# USB_To_UART.net
KiCad netlist of a schematic drawn in Altium Designer
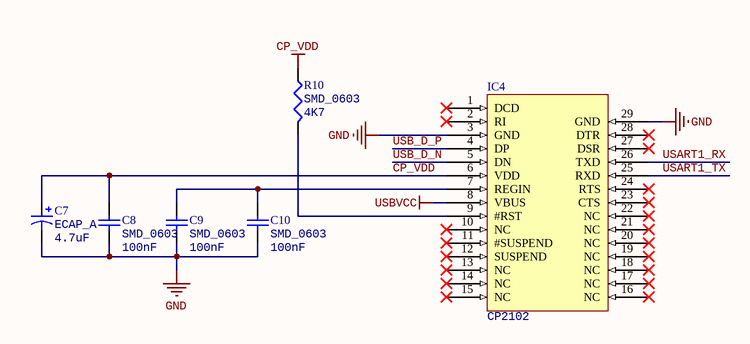
[diagram p0: USB_To_UART.SchDoc]

(export (version "E")
  (design (tool "Eeschema 10.0.6"))
  (components
    (comp (ref "C7")
      (value "ECAP_A")
      (footprint "CAPAE4645X63M")
      (description "Polarized Capacitor (Radial)")
      (fields (field (name "ALTIUM_VALUE") "4.7uF") (field (name "PUBLISHER") "Altium Limited"))
      (libsource (lib "Miscellaneous Devices") (part "Cap Pol1"))
    )
    (comp (ref "C8")
      (value "SMD_0603")
      (footprint "1608[0603]")
      (description "Capacitor (Semiconductor SIM Model)")
      (fields (field (name "ALTIUM_VALUE") "100nF") (field (name "PUBLISHER") "Altium Limited"))
      (libsource (lib "Miscellaneous Devices") (part "Cap Semi"))
    )
    (comp (ref "C9")
      (value "SMD_0603")
      (footprint "1608[0603]")
      (description "Capacitor (Semiconductor SIM Model)")
      (fields (field (name "ALTIUM_VALUE") "100nF") (field (name "PUBLISHER") "Altium Limited"))
      (libsource (lib "Miscellaneous Devices") (part "Cap Semi"))
    )
    (comp (ref "C10")
      (value "SMD_0603")
      (footprint "1608[0603]")
      (description "Capacitor (Semiconductor SIM Model)")
      (fields (field (name "ALTIUM_VALUE") "100nF") (field (name "PUBLISHER") "Altium Limited"))
      (libsource (lib "Miscellaneous Devices") (part "Cap Semi"))
    )
    (comp (ref "IC4")
      (value "CP2102")
      (footprint "QFN28")
      (description "Silabs CP2102")
      (libsource (lib "Components") (part "CP2102"))
    )
    (comp (ref "R10")
      (value "SMD_0603")
      (footprint "J1-0603")
      (description "Resistor")
      (fields (field (name "ALTIUM_VALUE") "4K7") (field (name "PUBLISHER") "Altium Limited"))
      (libsource (lib "Miscellaneous Devices") (part "Res3"))
    )
  )
  (nets
    (net (code "1") (name "/USART1_RX") (class "Default")
      (node (ref "IC4") (pin "26") (pinfunction "TXD_26") (pintype "input"))
    )
    (net (code "2") (name "/USART1_TX") (class "Default")
      (node (ref "IC4") (pin "25") (pinfunction "RXD_25") (pintype "input"))
    )
    (net (code "3") (name "/USB_D_N") (class "Default")
      (node (ref "IC4") (pin "5") (pinfunction "DN_5") (pintype "input"))
    )
    (net (code "4") (name "/USB_D_P") (class "Default")
      (node (ref "IC4") (pin "4") (pinfunction "DP_4") (pintype "input"))
    )
    (net (code "5") (name "CP_VDD") (class "Default")
      (node (ref "C7") (pin "1") (pinfunction "1_1") (pintype "passive"))
      (node (ref "C8") (pin "2") (pinfunction "2_2") (pintype "passive"))
      (node (ref "IC4") (pin "6") (pinfunction "VDD_6") (pintype "input"))
      (node (ref "R10") (pin "1") (pinfunction "1_1") (pintype "passive"))
    )
    (net (code "6") (name "GND") (class "Default")
      (node (ref "C10") (pin "1") (pinfunction "1_1") (pintype "passive"))
      (node (ref "C7") (pin "2") (pinfunction "2_2") (pintype "passive"))
      (node (ref "C8") (pin "1") (pinfunction "1_1") (pintype "passive"))
      (node (ref "C9") (pin "1") (pinfunction "1_1") (pintype "passive"))
      (node (ref "IC4") (pin "29") (pinfunction "GND_29") (pintype "input"))
      (node (ref "IC4") (pin "3") (pinfunction "GND_3") (pintype "input"))
    )
    (net (code "7") (name "Net-(IC4-#RST)") (class "Default")
      (node (ref "IC4") (pin "9") (pinfunction "#RST_9") (pintype "input"))
      (node (ref "R10") (pin "2") (pinfunction "2_2") (pintype "passive"))
    )
    (net (code "8") (name "Net-(IC4-REGIN)") (class "Default")
      (node (ref "C10") (pin "2") (pinfunction "2_2") (pintype "passive"))
      (node (ref "C9") (pin "2") (pinfunction "2_2") (pintype "passive"))
      (node (ref "IC4") (pin "7") (pinfunction "REGIN_7") (pintype "input"))
    )
    (net (code "9") (name "USBVCC") (class "Default")
      (node (ref "IC4") (pin "8") (pinfunction "VBUS_8") (pintype "input"))
    )
    (net (code "10") (name "unconnected-(IC4-#SUSPEND-Pad11)") (class "Default")
      (node (ref "IC4") (pin "11") (pinfunction "#SUSPEND_11") (pintype "input+no_connect"))
    )
    (net (code "11") (name "unconnected-(IC4-CTS-Pad23)") (class "Default")
      (node (ref "IC4") (pin "23") (pinfunction "CTS_23") (pintype "input+no_connect"))
    )
    (net (code "12") (name "unconnected-(IC4-DCD-Pad1)") (class "Default")
      (node (ref "IC4") (pin "1") (pinfunction "DCD_1") (pintype "input+no_connect"))
    )
    (net (code "13") (name "unconnected-(IC4-DSR-Pad27)") (class "Default")
      (node (ref "IC4") (pin "27") (pinfunction "DSR_27") (pintype "input+no_connect"))
    )
    (net (code "14") (name "unconnected-(IC4-DTR-Pad28)") (class "Default")
      (node (ref "IC4") (pin "28") (pinfunction "DTR_28") (pintype "input+no_connect"))
    )
    (net (code "15") (name "unconnected-(IC4-NC-Pad10)") (class "Default")
      (node (ref "IC4") (pin "10") (pinfunction "NC_10") (pintype "input+no_connect"))
    )
    (net (code "16") (name "unconnected-(IC4-NC-Pad13)") (class "Default")
      (node (ref "IC4") (pin "13") (pinfunction "NC_13") (pintype "input+no_connect"))
    )
    (net (code "17") (name "unconnected-(IC4-NC-Pad14)") (class "Default")
      (node (ref "IC4") (pin "14") (pinfunction "NC_14") (pintype "input+no_connect"))
    )
    (net (code "18") (name "unconnected-(IC4-NC-Pad15)") (class "Default")
      (node (ref "IC4") (pin "15") (pinfunction "NC_15") (pintype "input+no_connect"))
    )
    (net (code "19") (name "unconnected-(IC4-NC-Pad16)") (class "Default")
      (node (ref "IC4") (pin "16") (pinfunction "NC_16") (pintype "input+no_connect"))
    )
    (net (code "20") (name "unconnected-(IC4-NC-Pad17)") (class "Default")
      (node (ref "IC4") (pin "17") (pinfunction "NC_17") (pintype "input+no_connect"))
    )
    (net (code "21") (name "unconnected-(IC4-NC-Pad18)") (class "Default")
      (node (ref "IC4") (pin "18") (pinfunction "NC_18") (pintype "input+no_connect"))
    )
    (net (code "22") (name "unconnected-(IC4-NC-Pad19)") (class "Default")
      (node (ref "IC4") (pin "19") (pinfunction "NC_19") (pintype "input+no_connect"))
    )
    (net (code "23") (name "unconnected-(IC4-NC-Pad20)") (class "Default")
      (node (ref "IC4") (pin "20") (pinfunction "NC_20") (pintype "input+no_connect"))
    )
    (net (code "24") (name "unconnected-(IC4-NC-Pad21)") (class "Default")
      (node (ref "IC4") (pin "21") (pinfunction "NC_21") (pintype "input+no_connect"))
    )
    (net (code "25") (name "unconnected-(IC4-NC-Pad22)") (class "Default")
      (node (ref "IC4") (pin "22") (pinfunction "NC_22") (pintype "input+no_connect"))
    )
    (net (code "26") (name "unconnected-(IC4-RI-Pad2)") (class "Default")
      (node (ref "IC4") (pin "2") (pinfunction "RI_2") (pintype "input+no_connect"))
    )
    (net (code "27") (name "unconnected-(IC4-RTS-Pad24)") (class "Default")
      (node (ref "IC4") (pin "24") (pinfunction "RTS_24") (pintype "input+no_connect"))
    )
    (net (code "28") (name "unconnected-(IC4-SUSPEND-Pad12)") (class "Default")
      (node (ref "IC4") (pin "12") (pinfunction "SUSPEND_12") (pintype "input+no_connect"))
    )
  )
)
